# v1.net
KiCad netlist of a schematic drawn in EAGLE
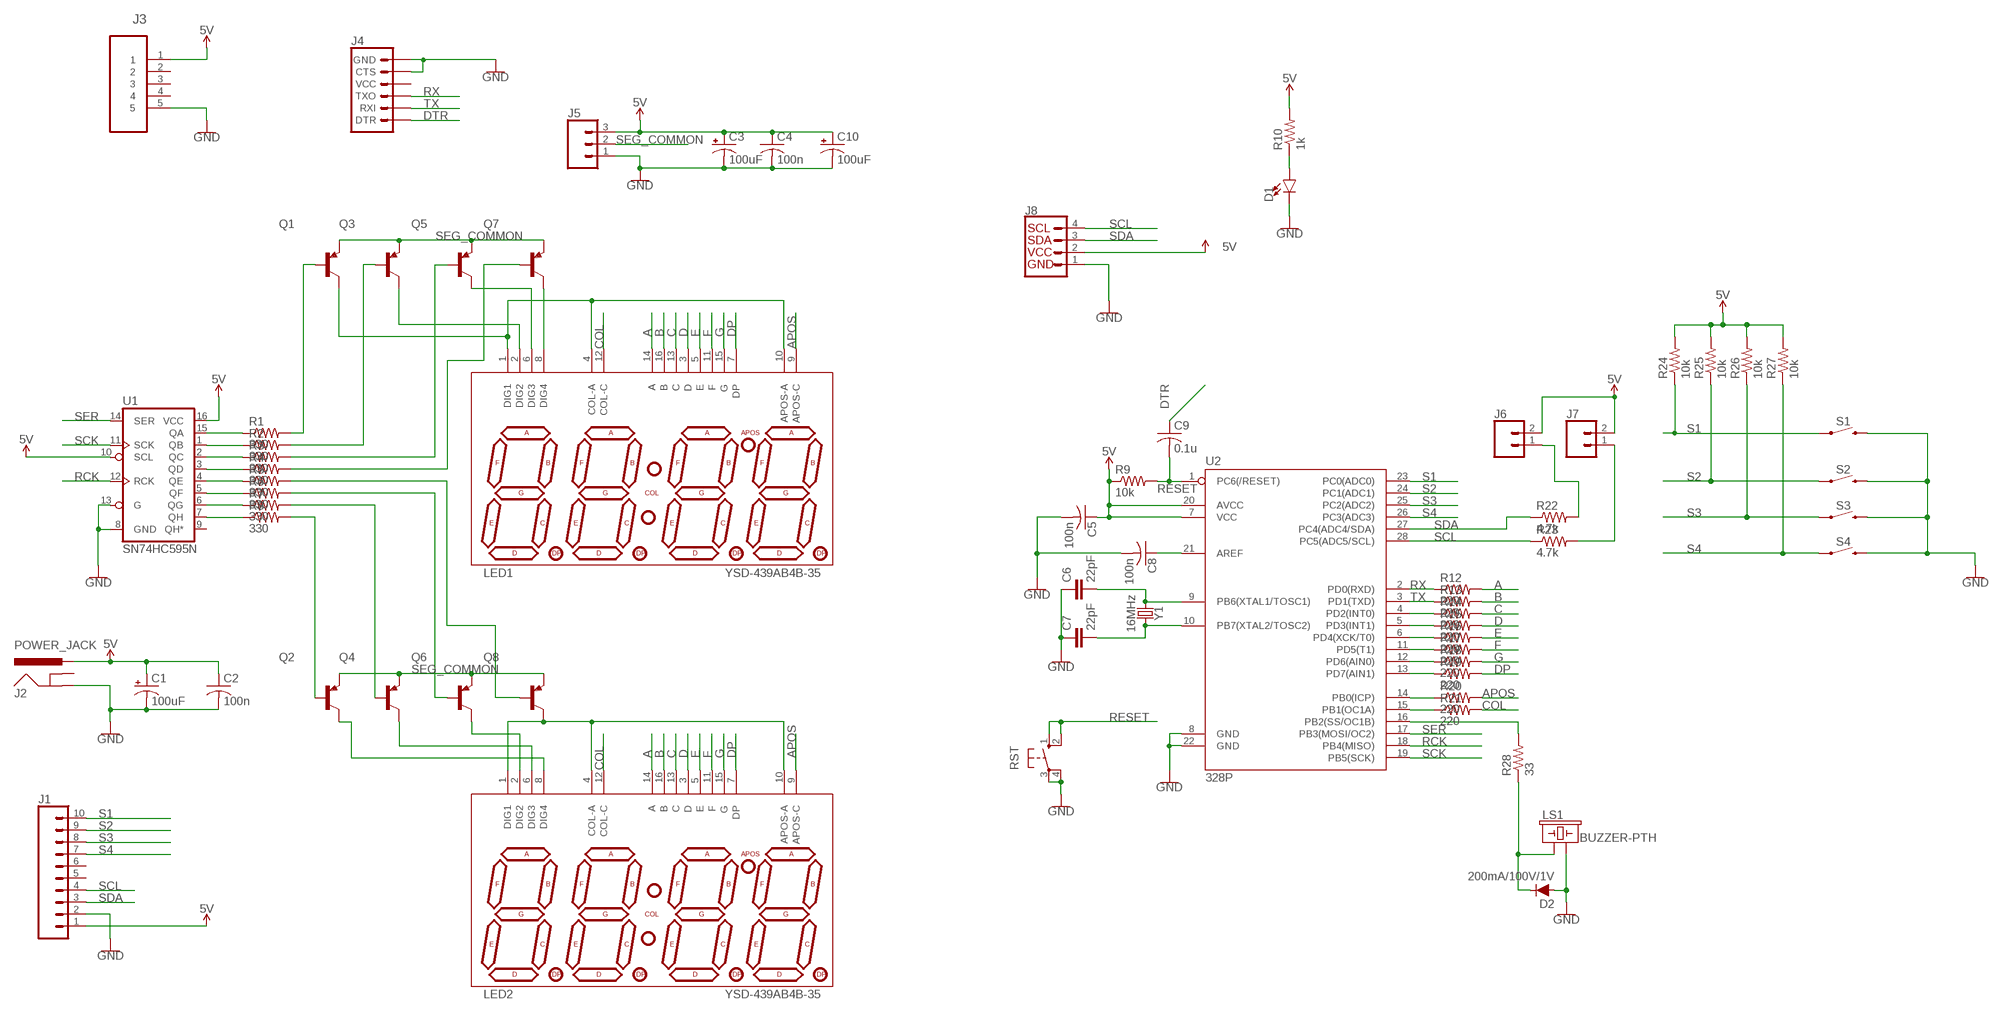
[diagram p0: schematic, sheet 1]

(export (version "E")
  (design (tool "Eeschema 10.0.6"))
  (components
    (comp (ref "C1")
      (value "100uF")
      (footprint "eagle-import:CPOL-RADIAL-2.5MM-6.5MM")
      (libsource (lib "eagle-import") (part "100UF-POLAR-RADIAL-2.5MM-25V-20%"))
    )
    (comp (ref "C2")
      (value "100n")
      (footprint "eagle-import:C025-025X050")
      (libsource (lib "eagle-import") (part "C-US025-025X050"))
    )
    (comp (ref "C3")
      (value "100uF")
      (footprint "eagle-import:CPOL-RADIAL-2.5MM-6.5MM")
      (libsource (lib "eagle-import") (part "100UF-POLAR-RADIAL-2.5MM-25V-20%"))
    )
    (comp (ref "C4")
      (value "100n")
      (footprint "eagle-import:C025-025X050")
      (libsource (lib "eagle-import") (part "C-US025-025X050"))
    )
    (comp (ref "C5")
      (value "100n")
      (footprint "eagle-import:C025-025X050")
      (libsource (lib "eagle-import") (part "C-US025-025X050"))
    )
    (comp (ref "C6")
      (value "22pF")
      (footprint "eagle-import:CAP-PTH-2.54")
      (libsource (lib "eagle-import") (part "22PF-PTH-2.54MM-200V-5%"))
    )
    (comp (ref "C7")
      (value "22pF")
      (footprint "eagle-import:CAP-PTH-2.54")
      (libsource (lib "eagle-import") (part "22PF-PTH-2.54MM-200V-5%"))
    )
    (comp (ref "C8")
      (value "100n")
      (footprint "eagle-import:C025-025X050")
      (libsource (lib "eagle-import") (part "C-US025-025X050"))
    )
    (comp (ref "C9")
      (value "0.1u")
      (footprint "eagle-import:C025-025X050")
      (libsource (lib "eagle-import") (part "C-US025-025X050"))
    )
    (comp (ref "C10")
      (value "100uF")
      (footprint "eagle-import:CPOL-RADIAL-2.5MM-6.5MM")
      (libsource (lib "eagle-import") (part "100UF-POLAR-RADIAL-2.5MM-25V-20%"))
    )
    (comp (ref "D1")
      (value "LED3MM")
      (footprint "eagle-import:LED_3MM")
      (libsource (lib "eagle-import") (part "LED3MM"))
    )
    (comp (ref "D2")
      (value "200mA/100V/1V")
      (footprint "eagle-import:DIODE-1N4148")
      (libsource (lib "eagle-import") (part "DIODE-1N4148"))
    )
    (comp (ref "J1")
      (value "CONN_10\"")
      (footprint "eagle-import:1X10")
      (libsource (lib "eagle-import") (part "CONN_10{dblquote}"))
    )
    (comp (ref "J2")
      (value "POWER_JACK")
      (footprint "eagle-import:POWER_JACK_PTH")
      (libsource (lib "eagle-import") (part "POWER_JACK"))
    )
    (comp (ref "J3")
      (value "47346-0001")
      (footprint "eagle-import:MOLEX_47346-0001")
      (libsource (lib "eagle-import") (part "47346-0001"))
    )
    (comp (ref "J4")
      (value "6_PIN_SERIAL_TARGET")
      (footprint "eagle-import:1X06")
      (libsource (lib "eagle-import") (part "6_PIN_SERIAL_TARGET"))
    )
    (comp (ref "J5")
      (value "CONN_03")
      (footprint "eagle-import:1X03")
      (libsource (lib "eagle-import") (part "CONN_03"))
    )
    (comp (ref "J6")
      (value "CONN_02")
      (footprint "eagle-import:1X02")
      (libsource (lib "eagle-import") (part "CONN_02"))
    )
    (comp (ref "J7")
      (value "CONN_02")
      (footprint "eagle-import:1X02")
      (libsource (lib "eagle-import") (part "CONN_02"))
    )
    (comp (ref "J8")
      (value "I2C_STANDARD")
      (footprint "eagle-import:1X04")
      (libsource (lib "eagle-import") (part "I2C_STANDARD"))
    )
    (comp (ref "LED1")
      (value "YSD-439AB4B-35")
      (footprint "eagle-import:7-SEGMENT-4DIGIT-YOUNGSUN")
      (libsource (lib "eagle-import") (part "7-SEGMENT-4DIGIT-10MM-BLUE"))
    )
    (comp (ref "LED2")
      (value "YSD-439AB4B-35")
      (footprint "eagle-import:7-SEGMENT-4DIGIT-YOUNGSUN")
      (libsource (lib "eagle-import") (part "7-SEGMENT-4DIGIT-10MM-BLUE"))
    )
    (comp (ref "LS1")
      (value "BUZZER-PTH")
      (footprint "eagle-import:BUZZER-12MM")
      (libsource (lib "eagle-import") (part "BUZZER-PTH"))
    )
    (comp (ref "Q1")
      (value "2N3906")
      (footprint "eagle-import:TO92")
      (libsource (lib "eagle-import") (part "2N3906"))
    )
    (comp (ref "Q2")
      (value "2N3906")
      (footprint "eagle-import:TO92")
      (libsource (lib "eagle-import") (part "2N3906"))
    )
    (comp (ref "Q3")
      (value "2N3906")
      (footprint "eagle-import:TO92")
      (libsource (lib "eagle-import") (part "2N3906"))
    )
    (comp (ref "Q4")
      (value "2N3906")
      (footprint "eagle-import:TO92")
      (libsource (lib "eagle-import") (part "2N3906"))
    )
    (comp (ref "Q5")
      (value "2N3906")
      (footprint "eagle-import:TO92")
      (libsource (lib "eagle-import") (part "2N3906"))
    )
    (comp (ref "Q6")
      (value "2N3906")
      (footprint "eagle-import:TO92")
      (libsource (lib "eagle-import") (part "2N3906"))
    )
    (comp (ref "Q7")
      (value "2N3906")
      (footprint "eagle-import:TO92")
      (libsource (lib "eagle-import") (part "2N3906"))
    )
    (comp (ref "Q8")
      (value "2N3906")
      (footprint "eagle-import:TO92")
      (libsource (lib "eagle-import") (part "2N3906"))
    )
    (comp (ref "R1")
      (value "330")
      (footprint "eagle-import:0204_5")
      (libsource (lib "eagle-import") (part "R-US_0204/5"))
    )
    (comp (ref "R2")
      (value "330")
      (footprint "eagle-import:0204_5")
      (libsource (lib "eagle-import") (part "R-US_0204/5"))
    )
    (comp (ref "R3")
      (value "330")
      (footprint "eagle-import:0204_5")
      (libsource (lib "eagle-import") (part "R-US_0204/5"))
    )
    (comp (ref "R4")
      (value "330")
      (footprint "eagle-import:0204_5")
      (libsource (lib "eagle-import") (part "R-US_0204/5"))
    )
    (comp (ref "R5")
      (value "330")
      (footprint "eagle-import:0204_5")
      (libsource (lib "eagle-import") (part "R-US_0204/5"))
    )
    (comp (ref "R6")
      (value "330")
      (footprint "eagle-import:0204_5")
      (libsource (lib "eagle-import") (part "R-US_0204/5"))
    )
    (comp (ref "R7")
      (value "330")
      (footprint "eagle-import:0204_5")
      (libsource (lib "eagle-import") (part "R-US_0204/5"))
    )
    (comp (ref "R8")
      (value "330")
      (footprint "eagle-import:0204_5")
      (libsource (lib "eagle-import") (part "R-US_0204/5"))
    )
    (comp (ref "R9")
      (value "10k")
      (footprint "eagle-import:0204_5")
      (libsource (lib "eagle-import") (part "R-US_0204/5"))
    )
    (comp (ref "R10")
      (value "1k")
      (footprint "eagle-import:0204_5")
      (libsource (lib "eagle-import") (part "R-US_0204/5"))
    )
    (comp (ref "R12")
      (value "220")
      (footprint "eagle-import:0204_5")
      (libsource (lib "eagle-import") (part "R-US_0204/5"))
    )
    (comp (ref "R13")
      (value "220")
      (footprint "eagle-import:0204_5")
      (libsource (lib "eagle-import") (part "R-US_0204/5"))
    )
    (comp (ref "R14")
      (value "220")
      (footprint "eagle-import:0204_5")
      (libsource (lib "eagle-import") (part "R-US_0204/5"))
    )
    (comp (ref "R15")
      (value "220")
      (footprint "eagle-import:0204_5")
      (libsource (lib "eagle-import") (part "R-US_0204/5"))
    )
    (comp (ref "R16")
      (value "220")
      (footprint "eagle-import:0204_5")
      (libsource (lib "eagle-import") (part "R-US_0204/5"))
    )
    (comp (ref "R17")
      (value "220")
      (footprint "eagle-import:0204_5")
      (libsource (lib "eagle-import") (part "R-US_0204/5"))
    )
    (comp (ref "R18")
      (value "220")
      (footprint "eagle-import:0204_5")
      (libsource (lib "eagle-import") (part "R-US_0204/5"))
    )
    (comp (ref "R19")
      (value "220")
      (footprint "eagle-import:0204_5")
      (libsource (lib "eagle-import") (part "R-US_0204/5"))
    )
    (comp (ref "R20")
      (value "220")
      (footprint "eagle-import:0204_5")
      (libsource (lib "eagle-import") (part "R-US_0204/5"))
    )
    (comp (ref "R21")
      (value "220")
      (footprint "eagle-import:0204_5")
      (libsource (lib "eagle-import") (part "R-US_0204/5"))
    )
    (comp (ref "R22")
      (value "4.7k")
      (footprint "eagle-import:0204_5")
      (libsource (lib "eagle-import") (part "R-US_0204/5"))
    )
    (comp (ref "R23")
      (value "4.7k")
      (footprint "eagle-import:0204_5")
      (libsource (lib "eagle-import") (part "R-US_0204/5"))
    )
    (comp (ref "R24")
      (value "10k")
      (footprint "eagle-import:0204_5")
      (libsource (lib "eagle-import") (part "R-US_0204/5"))
    )
    (comp (ref "R25")
      (value "10k")
      (footprint "eagle-import:0204_5")
      (libsource (lib "eagle-import") (part "R-US_0204/5"))
    )
    (comp (ref "R26")
      (value "10k")
      (footprint "eagle-import:0204_5")
      (libsource (lib "eagle-import") (part "R-US_0204/5"))
    )
    (comp (ref "R27")
      (value "10k")
      (footprint "eagle-import:0204_5")
      (libsource (lib "eagle-import") (part "R-US_0204/5"))
    )
    (comp (ref "R28")
      (value "33")
      (footprint "eagle-import:0204_5")
      (libsource (lib "eagle-import") (part "R-US_0204/5"))
    )
    (comp (ref "RST")
      (value "10-XX")
      (footprint "eagle-import:B3F-10XX")
      (fields (field (name "MPN") "B3F-1000"))
      (libsource (lib "eagle-import") (part "10-XX"))
    )
    (comp (ref "S1")
      (value "MOMENTARY-SWITCH-SPST-PTH-6.0MM")
      (footprint "eagle-import:TACTILE_SWITCH_PTH_6.0MM")
      (libsource (lib "eagle-import") (part "MOMENTARY-SWITCH-SPST-PTH-6.0MM"))
    )
    (comp (ref "S2")
      (value "MOMENTARY-SWITCH-SPST-PTH-6.0MM")
      (footprint "eagle-import:TACTILE_SWITCH_PTH_6.0MM")
      (libsource (lib "eagle-import") (part "MOMENTARY-SWITCH-SPST-PTH-6.0MM"))
    )
    (comp (ref "S3")
      (value "MOMENTARY-SWITCH-SPST-PTH-6.0MM")
      (footprint "eagle-import:TACTILE_SWITCH_PTH_6.0MM")
      (libsource (lib "eagle-import") (part "MOMENTARY-SWITCH-SPST-PTH-6.0MM"))
    )
    (comp (ref "S4")
      (value "MOMENTARY-SWITCH-SPST-PTH-6.0MM")
      (footprint "eagle-import:TACTILE_SWITCH_PTH_6.0MM")
      (libsource (lib "eagle-import") (part "MOMENTARY-SWITCH-SPST-PTH-6.0MM"))
    )
    (comp (ref "U1")
      (value "SN74HC595N")
      (footprint "eagle-import:DIP16")
      (libsource (lib "eagle-import") (part "74595NHC"))
    )
    (comp (ref "U2")
      (value "328P")
      (footprint "eagle-import:DIP28")
      (libsource (lib "eagle-import") (part "ATMEGA328P_PDIP"))
    )
    (comp (ref "Y1")
      (value "16MHz")
      (footprint "eagle-import:HC49US")
      (libsource (lib "eagle-import") (part "CRYSTAL-16MHZPTH-HC49US"))
    )
  )
  (nets
    (net (code "1") (name "/A") (class "Default")
      (node (ref "LED1") (pin "14") (pinfunction "A_14") (pintype "bidirectional"))
      (node (ref "LED2") (pin "14") (pinfunction "A_14") (pintype "bidirectional"))
      (node (ref "R12") (pin "2") (pinfunction "2_2") (pintype "passive"))
    )
    (net (code "2") (name "/APOS") (class "Default")
      (node (ref "LED1") (pin "9") (pinfunction "APOS-C_9") (pintype "bidirectional"))
      (node (ref "LED2") (pin "9") (pinfunction "APOS-C_9") (pintype "bidirectional"))
      (node (ref "R20") (pin "2") (pinfunction "2_2") (pintype "passive"))
    )
    (net (code "3") (name "/B") (class "Default")
      (node (ref "LED1") (pin "16") (pinfunction "B_16") (pintype "bidirectional"))
      (node (ref "LED2") (pin "16") (pinfunction "B_16") (pintype "bidirectional"))
      (node (ref "R13") (pin "2") (pinfunction "2_2") (pintype "passive"))
    )
    (net (code "4") (name "/C") (class "Default")
      (node (ref "LED1") (pin "13") (pinfunction "C_13") (pintype "bidirectional"))
      (node (ref "LED2") (pin "13") (pinfunction "C_13") (pintype "bidirectional"))
      (node (ref "R14") (pin "2") (pinfunction "2_2") (pintype "passive"))
    )
    (net (code "5") (name "/COL") (class "Default")
      (node (ref "LED1") (pin "12") (pinfunction "COL-C_12") (pintype "bidirectional"))
      (node (ref "LED2") (pin "12") (pinfunction "COL-C_12") (pintype "bidirectional"))
      (node (ref "R21") (pin "2") (pinfunction "2_2") (pintype "passive"))
    )
    (net (code "6") (name "/D") (class "Default")
      (node (ref "LED1") (pin "3") (pinfunction "D_3") (pintype "bidirectional"))
      (node (ref "LED2") (pin "3") (pinfunction "D_3") (pintype "bidirectional"))
      (node (ref "R15") (pin "2") (pinfunction "2_2") (pintype "passive"))
    )
    (net (code "7") (name "/DP") (class "Default")
      (node (ref "LED1") (pin "7") (pinfunction "DP_7") (pintype "bidirectional"))
      (node (ref "LED2") (pin "7") (pinfunction "DP_7") (pintype "bidirectional"))
      (node (ref "R19") (pin "2") (pinfunction "2_2") (pintype "passive"))
    )
    (net (code "8") (name "/DTR") (class "Default")
      (node (ref "C9") (pin "1") (pinfunction "1_1") (pintype "passive"))
      (node (ref "J4") (pin "1") (pinfunction "DTR_1") (pintype "passive"))
    )
    (net (code "9") (name "/E") (class "Default")
      (node (ref "LED1") (pin "5") (pinfunction "E_5") (pintype "bidirectional"))
      (node (ref "LED2") (pin "5") (pinfunction "E_5") (pintype "bidirectional"))
      (node (ref "R16") (pin "2") (pinfunction "2_2") (pintype "passive"))
    )
    (net (code "10") (name "/F") (class "Default")
      (node (ref "LED1") (pin "11") (pinfunction "F_11") (pintype "bidirectional"))
      (node (ref "LED2") (pin "11") (pinfunction "F_11") (pintype "bidirectional"))
      (node (ref "R17") (pin "2") (pinfunction "2_2") (pintype "passive"))
    )
    (net (code "11") (name "/G") (class "Default")
      (node (ref "LED1") (pin "15") (pinfunction "G_15") (pintype "bidirectional"))
      (node (ref "LED2") (pin "15") (pinfunction "G_15") (pintype "bidirectional"))
      (node (ref "R18") (pin "2") (pinfunction "2_2") (pintype "passive"))
    )
    (net (code "12") (name "/RCK") (class "Default")
      (node (ref "U1") (pin "12") (pinfunction "RCK_12") (pintype "input"))
      (node (ref "U2") (pin "18") (pinfunction "PB4(MISO)_18") (pintype "bidirectional"))
    )
    (net (code "13") (name "/RESET") (class "Default")
      (node (ref "C9") (pin "2") (pinfunction "2_2") (pintype "passive"))
      (node (ref "R9") (pin "2") (pinfunction "2_2") (pintype "passive"))
      (node (ref "RST") (pin "1") (pinfunction "S_1") (pintype "passive"))
      (node (ref "RST") (pin "2") (pinfunction "S1_2") (pintype "passive"))
      (node (ref "U2") (pin "1") (pinfunction "PC6(/RESET)_1") (pintype "bidirectional"))
    )
    (net (code "14") (name "/RX") (class "Default")
      (node (ref "J4") (pin "3") (pinfunction "TXO_3") (pintype "passive"))
      (node (ref "R12") (pin "1") (pinfunction "1_1") (pintype "passive"))
      (node (ref "U2") (pin "2") (pinfunction "PD0(RXD)_2") (pintype "bidirectional"))
    )
    (net (code "15") (name "/S1") (class "Default")
      (node (ref "J1") (pin "10") (pinfunction "10_10") (pintype "passive"))
      (node (ref "R24") (pin "1") (pinfunction "1_1") (pintype "passive"))
      (node (ref "S1") (pin "1") (pinfunction "1_1") (pintype "passive"))
      (node (ref "U2") (pin "23") (pinfunction "PC0(ADC0)_23") (pintype "bidirectional"))
    )
    (net (code "16") (name "/S2") (class "Default")
      (node (ref "J1") (pin "9") (pinfunction "9_9") (pintype "passive"))
      (node (ref "R25") (pin "1") (pinfunction "1_1") (pintype "passive"))
      (node (ref "S2") (pin "1") (pinfunction "1_1") (pintype "passive"))
      (node (ref "U2") (pin "24") (pinfunction "PC1(ADC1)_24") (pintype "bidirectional"))
    )
    (net (code "17") (name "/S3") (class "Default")
      (node (ref "J1") (pin "8") (pinfunction "8_8") (pintype "passive"))
      (node (ref "R26") (pin "1") (pinfunction "1_1") (pintype "passive"))
      (node (ref "S3") (pin "1") (pinfunction "1_1") (pintype "passive"))
      (node (ref "U2") (pin "25") (pinfunction "PC2(ADC2)_25") (pintype "bidirectional"))
    )
    (net (code "18") (name "/S4") (class "Default")
      (node (ref "J1") (pin "7") (pinfunction "7_7") (pintype "passive"))
      (node (ref "R27") (pin "1") (pinfunction "1_1") (pintype "passive"))
      (node (ref "S4") (pin "1") (pinfunction "1_1") (pintype "passive"))
      (node (ref "U2") (pin "26") (pinfunction "PC3(ADC3)_26") (pintype "bidirectional"))
    )
    (net (code "19") (name "/SCK") (class "Default")
      (node (ref "U1") (pin "11") (pinfunction "SCK_11") (pintype "input"))
      (node (ref "U2") (pin "19") (pinfunction "PB5(SCK)_19") (pintype "bidirectional"))
    )
    (net (code "20") (name "/SCL") (class "Default")
      (node (ref "J1") (pin "4") (pinfunction "4_4") (pintype "passive"))
      (node (ref "J8") (pin "4") (pinfunction "4_4") (pintype "passive"))
      (node (ref "R23") (pin "1") (pinfunction "1_1") (pintype "passive"))
      (node (ref "U2") (pin "28") (pinfunction "PC5(ADC5/SCL)_28") (pintype "bidirectional"))
    )
    (net (code "21") (name "/SDA") (class "Default")
      (node (ref "J1") (pin "3") (pinfunction "3_3") (pintype "passive"))
      (node (ref "J8") (pin "3") (pinfunction "3_3") (pintype "passive"))
      (node (ref "R22") (pin "1") (pinfunction "1_1") (pintype "passive"))
      (node (ref "U2") (pin "27") (pinfunction "PC4(ADC4/SDA)_27") (pintype "bidirectional"))
    )
    (net (code "22") (name "/SEG_COMMON") (class "Default")
      (node (ref "J5") (pin "2") (pinfunction "2_2") (pintype "passive"))
      (node (ref "Q1") (pin "3") (pinfunction "E_3") (pintype "passive"))
      (node (ref "Q2") (pin "3") (pinfunction "E_3") (pintype "passive"))
      (node (ref "Q3") (pin "3") (pinfunction "E_3") (pintype "passive"))
      (node (ref "Q4") (pin "3") (pinfunction "E_3") (pintype "passive"))
      (node (ref "Q5") (pin "3") (pinfunction "E_3") (pintype "passive"))
      (node (ref "Q6") (pin "3") (pinfunction "E_3") (pintype "passive"))
      (node (ref "Q7") (pin "3") (pinfunction "E_3") (pintype "passive"))
      (node (ref "Q8") (pin "3") (pinfunction "E_3") (pintype "passive"))
    )
    (net (code "23") (name "/SER") (class "Default")
      (node (ref "U1") (pin "14") (pinfunction "SER_14") (pintype "input"))
      (node (ref "U2") (pin "17") (pinfunction "PB3(MOSI/OC2)_17") (pintype "bidirectional"))
    )
    (net (code "24") (name "/TX") (class "Default")
      (node (ref "J4") (pin "2") (pinfunction "RXI_2") (pintype "passive"))
      (node (ref "R13") (pin "1") (pinfunction "1_1") (pintype "passive"))
      (node (ref "U2") (pin "3") (pinfunction "PD1(TXD)_3") (pintype "bidirectional"))
    )
    (net (code "25") (name "5V") (class "Default")
      (node (ref "C1") (pin "1") (pinfunction "+_1") (pintype "passive"))
      (node (ref "C10") (pin "1") (pinfunction "+_1") (pintype "passive"))
      (node (ref "C2") (pin "1") (pinfunction "1_1") (pintype "passive"))
      (node (ref "C3") (pin "1") (pinfunction "+_1") (pintype "passive"))
      (node (ref "C4") (pin "1") (pinfunction "1_1") (pintype "passive"))
      (node (ref "C5") (pin "1") (pinfunction "1_1") (pintype "passive"))
      (node (ref "J1") (pin "1") (pinfunction "1_1") (pintype "passive"))
      (node (ref "J2") (pin "PWR") (pinfunction "PWR_PWR") (pintype "bidirectional"))
      (node (ref "J3") (pin "1") (pinfunction "1_1") (pintype "input"))
      (node (ref "J5") (pin "3") (pinfunction "3_3") (pintype "passive"))
      (node (ref "J6") (pin "2") (pinfunction "2_2") (pintype "passive"))
      (node (ref "J7") (pin "2") (pinfunction "2_2") (pintype "passive"))
      (node (ref "J8") (pin "2") (pinfunction "2_2") (pintype "power_in"))
      (node (ref "R10") (pin "2") (pinfunction "2_2") (pintype "passive"))
      (node (ref "R24") (pin "2") (pinfunction "2_2") (pintype "passive"))
      (node (ref "R25") (pin "2") (pinfunction "2_2") (pintype "passive"))
      (node (ref "R26") (pin "2") (pinfunction "2_2") (pintype "passive"))
      (node (ref "R27") (pin "2") (pinfunction "2_2") (pintype "passive"))
      (node (ref "R9") (pin "1") (pinfunction "1_1") (pintype "passive"))
      (node (ref "U1") (pin "10") (pinfunction "SCL_10") (pintype "input"))
      (node (ref "U1") (pin "16") (pinfunction "VCC_16") (pintype "power_in"))
      (node (ref "U2") (pin "20") (pinfunction "AVCC_20") (pintype "bidirectional"))
      (node (ref "U2") (pin "7") (pinfunction "VCC_7") (pintype "bidirectional"))
    )
    (net (code "26") (name "GND") (class "Default")
      (node (ref "C1") (pin "2") (pinfunction "-_2") (pintype "passive"))
      (node (ref "C10") (pin "2") (pinfunction "-_2") (pintype "passive"))
      (node (ref "C2") (pin "2") (pinfunction "2_2") (pintype "passive"))
      (node (ref "C3") (pin "2") (pinfunction "-_2") (pintype "passive"))
      (node (ref "C4") (pin "2") (pinfunction "2_2") (pintype "passive"))
      (node (ref "C5") (pin "2") (pinfunction "2_2") (pintype "passive"))
      (node (ref "C6") (pin "1") (pinfunction "1_1") (pintype "passive"))
      (node (ref "C7") (pin "1") (pinfunction "1_1") (pintype "passive"))
      (node (ref "C8") (pin "2") (pinfunction "2_2") (pintype "passive"))
      (node (ref "D1") (pin "K") (pinfunction "C_K") (pintype "passive"))
      (node (ref "D2") (pin "A") (pinfunction "A_A") (pintype "passive"))
      (node (ref "J1") (pin "2") (pinfunction "2_2") (pintype "passive"))
      (node (ref "J2") (pin "GND") (pinfunction "GND_GND") (pintype "bidirectional"))
      (node (ref "J3") (pin "5") (pinfunction "5_5") (pintype "input"))
      (node (ref "J4") (pin "5") (pinfunction "CTS_5") (pintype "passive"))
      (node (ref "J4") (pin "6") (pinfunction "GND_6") (pintype "passive"))
      (node (ref "J5") (pin "1") (pinfunction "1_1") (pintype "passive"))
      (node (ref "J8") (pin "1") (pinfunction "1_1") (pintype "power_in"))
      (node (ref "LS1") (pin "-") (pinfunction "2_-") (pintype "passive"))
      (node (ref "RST") (pin "3") (pinfunction "P_3") (pintype "passive"))
      (node (ref "RST") (pin "4") (pinfunction "P1_4") (pintype "passive"))
      (node (ref "S1") (pin "3") (pinfunction "2_3") (pintype "passive"))
      (node (ref "S2") (pin "3") (pinfunction "2_3") (pintype "passive"))
      (node (ref "S3") (pin "3") (pinfunction "2_3") (pintype "passive"))
      (node (ref "S4") (pin "3") (pinfunction "2_3") (pintype "passive"))
      (node (ref "U1") (pin "13") (pinfunction "G_13") (pintype "input"))
      (node (ref "U1") (pin "8") (pinfunction "GND_8") (pintype "power_in"))
      (node (ref "U2") (pin "22") (pinfunction "GND_22") (pintype "bidirectional"))
      (node (ref "U2") (pin "8") (pinfunction "GND_8") (pintype "bidirectional"))
    )
    (net (code "27") (name "Net-(D1-PadA)") (class "Default")
      (node (ref "D1") (pin "A") (pinfunction "A_A") (pintype "passive"))
      (node (ref "R10") (pin "1") (pinfunction "1_1") (pintype "passive"))
    )
    (net (code "28") (name "Net-(J6-Pad1)") (class "Default")
      (node (ref "J6") (pin "1") (pinfunction "1_1") (pintype "passive"))
      (node (ref "R22") (pin "2") (pinfunction "2_2") (pintype "passive"))
    )
    (net (code "29") (name "Net-(J7-Pad1)") (class "Default")
      (node (ref "J7") (pin "1") (pinfunction "1_1") (pintype "passive"))
      (node (ref "R23") (pin "2") (pinfunction "2_2") (pintype "passive"))
    )
    (net (code "30") (name "Net-(LED1-APOS-A)") (class "Default")
      (node (ref "LED1") (pin "1") (pinfunction "DIG1_1") (pintype "bidirectional"))
      (node (ref "LED1") (pin "10") (pinfunction "APOS-A_10") (pintype "bidirectional"))
      (node (ref "LED1") (pin "4") (pinfunction "COL-A_4") (pintype "bidirectional"))
      (node (ref "Q1") (pin "1") (pinfunction "C_1") (pintype "passive"))
    )
    (net (code "31") (name "Net-(LED1-DIG2)") (class "Default")
      (node (ref "LED1") (pin "2") (pinfunction "DIG2_2") (pintype "bidirectional"))
      (node (ref "Q3") (pin "1") (pinfunction "C_1") (pintype "passive"))
    )
    (net (code "32") (name "Net-(LED1-DIG3)") (class "Default")
      (node (ref "LED1") (pin "6") (pinfunction "DIG3_6") (pintype "bidirectional"))
      (node (ref "Q5") (pin "1") (pinfunction "C_1") (pintype "passive"))
    )
    (net (code "33") (name "Net-(LED1-DIG4)") (class "Default")
      (node (ref "LED1") (pin "8") (pinfunction "DIG4_8") (pintype "bidirectional"))
      (node (ref "Q7") (pin "1") (pinfunction "C_1") (pintype "passive"))
    )
    (net (code "34") (name "Net-(LED2-APOS-A)") (class "Default")
      (node (ref "LED2") (pin "1") (pinfunction "DIG1_1") (pintype "bidirectional"))
      (node (ref "LED2") (pin "10") (pinfunction "APOS-A_10") (pintype "bidirectional"))
      (node (ref "LED2") (pin "4") (pinfunction "COL-A_4") (pintype "bidirectional"))
      (node (ref "Q8") (pin "1") (pinfunction "C_1") (pintype "passive"))
    )
    (net (code "35") (name "Net-(LED2-DIG2)") (class "Default")
      (node (ref "LED2") (pin "2") (pinfunction "DIG2_2") (pintype "bidirectional"))
      (node (ref "Q6") (pin "1") (pinfunction "C_1") (pintype "passive"))
    )
    (net (code "36") (name "Net-(LED2-DIG3)") (class "Default")
      (node (ref "LED2") (pin "6") (pinfunction "DIG3_6") (pintype "bidirectional"))
      (node (ref "Q4") (pin "1") (pinfunction "C_1") (pintype "passive"))
    )
    (net (code "37") (name "Net-(LED2-DIG4)") (class "Default")
      (node (ref "LED2") (pin "8") (pinfunction "DIG4_8") (pintype "bidirectional"))
      (node (ref "Q2") (pin "1") (pinfunction "C_1") (pintype "passive"))
    )
    (net (code "38") (name "Net-(LS1-1)") (class "Default")
      (node (ref "D2") (pin "C") (pinfunction "C_C") (pintype "passive"))
      (node (ref "LS1") (pin "+") (pinfunction "1_+") (pintype "passive"))
      (node (ref "R28") (pin "1") (pinfunction "1_1") (pintype "passive"))
    )
    (net (code "39") (name "Net-(Q1-B)") (class "Default")
      (node (ref "Q1") (pin "2") (pinfunction "B_2") (pintype "passive"))
      (node (ref "R1") (pin "2") (pinfunction "2_2") (pintype "passive"))
    )
    (net (code "40") (name "Net-(Q2-B)") (class "Default")
      (node (ref "Q2") (pin "2") (pinfunction "B_2") (pintype "passive"))
      (node (ref "R8") (pin "2") (pinfunction "2_2") (pintype "passive"))
    )
    (net (code "41") (name "Net-(Q3-B)") (class "Default")
      (node (ref "Q3") (pin "2") (pinfunction "B_2") (pintype "passive"))
      (node (ref "R2") (pin "2") (pinfunction "2_2") (pintype "passive"))
    )
    (net (code "42") (name "Net-(Q4-B)") (class "Default")
      (node (ref "Q4") (pin "2") (pinfunction "B_2") (pintype "passive"))
      (node (ref "R7") (pin "2") (pinfunction "2_2") (pintype "passive"))
    )
    (net (code "43") (name "Net-(Q5-B)") (class "Default")
      (node (ref "Q5") (pin "2") (pinfunction "B_2") (pintype "passive"))
      (node (ref "R3") (pin "2") (pinfunction "2_2") (pintype "passive"))
    )
    (net (code "44") (name "Net-(Q6-B)") (class "Default")
      (node (ref "Q6") (pin "2") (pinfunction "B_2") (pintype "passive"))
      (node (ref "R6") (pin "2") (pinfunction "2_2") (pintype "passive"))
    )
    (net (code "45") (name "Net-(Q7-B)") (class "Default")
      (node (ref "Q7") (pin "2") (pinfunction "B_2") (pintype "passive"))
      (node (ref "R4") (pin "2") (pinfunction "2_2") (pintype "passive"))
    )
    (net (code "46") (name "Net-(Q8-B)") (class "Default")
      (node (ref "Q8") (pin "2") (pinfunction "B_2") (pintype "passive"))
      (node (ref "R5") (pin "2") (pinfunction "2_2") (pintype "passive"))
    )
    (net (code "47") (name "Net-(U1-QA)") (class "Default")
      (node (ref "R1") (pin "1") (pinfunction "1_1") (pintype "passive"))
      (node (ref "U1") (pin "15") (pinfunction "QA_15") (pintype "tri_state"))
    )
    (net (code "48") (name "Net-(U1-QB)") (class "Default")
      (node (ref "R2") (pin "1") (pinfunction "1_1") (pintype "passive"))
      (node (ref "U1") (pin "1") (pinfunction "QB_1") (pintype "tri_state"))
    )
    (net (code "49") (name "Net-(U1-QC)") (class "Default")
      (node (ref "R3") (pin "1") (pinfunction "1_1") (pintype "passive"))
      (node (ref "U1") (pin "2") (pinfunction "QC_2") (pintype "tri_state"))
    )
    (net (code "50") (name "Net-(U1-QD)") (class "Default")
      (node (ref "R4") (pin "1") (pinfunction "1_1") (pintype "passive"))
      (node (ref "U1") (pin "3") (pinfunction "QD_3") (pintype "tri_state"))
    )
    (net (code "51") (name "Net-(U1-QE)") (class "Default")
      (node (ref "R5") (pin "1") (pinfunction "1_1") (pintype "passive"))
      (node (ref "U1") (pin "4") (pinfunction "QE_4") (pintype "tri_state"))
    )
    (net (code "52") (name "Net-(U1-QF)") (class "Default")
      (node (ref "R6") (pin "1") (pinfunction "1_1") (pintype "passive"))
      (node (ref "U1") (pin "5") (pinfunction "QF_5") (pintype "tri_state"))
    )
    (net (code "53") (name "Net-(U1-QG)") (class "Default")
      (node (ref "R7") (pin "1") (pinfunction "1_1") (pintype "passive"))
      (node (ref "U1") (pin "6") (pinfunction "QG_6") (pintype "tri_state"))
    )
    (net (code "54") (name "Net-(U1-QH)") (class "Default")
      (node (ref "R8") (pin "1") (pinfunction "1_1") (pintype "passive"))
      (node (ref "U1") (pin "7") (pinfunction "QH_7") (pintype "tri_state"))
    )
    (net (code "55") (name "Net-(U2-AREF)") (class "Default")
      (node (ref "C8") (pin "1") (pinfunction "1_1") (pintype "passive"))
      (node (ref "U2") (pin "21") (pinfunction "AREF_21") (pintype "bidirectional"))
    )
    (net (code "56") (name "Net-(U2-PB0(ICP))") (class "Default")
      (node (ref "R20") (pin "1") (pinfunction "1_1") (pintype "passive"))
      (node (ref "U2") (pin "14") (pinfunction "PB0(ICP)_14") (pintype "bidirectional"))
    )
    (net (code "57") (name "Net-(U2-PB1(OC1A))") (class "Default")
      (node (ref "R21") (pin "1") (pinfunction "1_1") (pintype "passive"))
      (node (ref "U2") (pin "15") (pinfunction "PB1(OC1A)_15") (pintype "bidirectional"))
    )
    (net (code "58") (name "Net-(U2-PB2(SS{slash}OC1B))") (class "Default")
      (node (ref "R28") (pin "2") (pinfunction "2_2") (pintype "passive"))
      (node (ref "U2") (pin "16") (pinfunction "PB2(SS/OC1B)_16") (pintype "bidirectional"))
    )
    (net (code "59") (name "Net-(U2-PB6(XTAL1{slash}TOSC1))") (class "Default")
      (node (ref "C6") (pin "2") (pinfunction "2_2") (pintype "passive"))
      (node (ref "U2") (pin "9") (pinfunction "PB6(XTAL1/TOSC1)_9") (pintype "bidirectional"))
      (node (ref "Y1") (pin "1") (pinfunction "1_1") (pintype "passive"))
    )
    (net (code "60") (name "Net-(U2-PB7(XTAL2{slash}TOSC2))") (class "Default")
      (node (ref "C7") (pin "2") (pinfunction "2_2") (pintype "passive"))
      (node (ref "U2") (pin "10") (pinfunction "PB7(XTAL2/TOSC2)_10") (pintype "bidirectional"))
      (node (ref "Y1") (pin "2") (pinfunction "2_2") (pintype "passive"))
    )
    (net (code "61") (name "Net-(U2-PD2(INT0))") (class "Default")
      (node (ref "R14") (pin "1") (pinfunction "1_1") (pintype "passive"))
      (node (ref "U2") (pin "4") (pinfunction "PD2(INT0)_4") (pintype "bidirectional"))
    )
    (net (code "62") (name "Net-(U2-PD3(INT1))") (class "Default")
      (node (ref "R15") (pin "1") (pinfunction "1_1") (pintype "passive"))
      (node (ref "U2") (pin "5") (pinfunction "PD3(INT1)_5") (pintype "bidirectional"))
    )
    (net (code "63") (name "Net-(U2-PD4(XCK{slash}T0))") (class "Default")
      (node (ref "R16") (pin "1") (pinfunction "1_1") (pintype "passive"))
      (node (ref "U2") (pin "6") (pinfunction "PD4(XCK/T0)_6") (pintype "bidirectional"))
    )
    (net (code "64") (name "Net-(U2-PD5(T1))") (class "Default")
      (node (ref "R17") (pin "1") (pinfunction "1_1") (pintype "passive"))
      (node (ref "U2") (pin "11") (pinfunction "PD5(T1)_11") (pintype "bidirectional"))
    )
    (net (code "65") (name "Net-(U2-PD6(AIN0))") (class "Default")
      (node (ref "R18") (pin "1") (pinfunction "1_1") (pintype "passive"))
      (node (ref "U2") (pin "12") (pinfunction "PD6(AIN0)_12") (pintype "bidirectional"))
    )
    (net (code "66") (name "Net-(U2-PD7(AIN1))") (class "Default")
      (node (ref "R19") (pin "1") (pinfunction "1_1") (pintype "passive"))
      (node (ref "U2") (pin "13") (pinfunction "PD7(AIN1)_13") (pintype "bidirectional"))
    )
    (net (code "67") (name "unconnected-(J1-Pad5)") (class "Default")
      (node (ref "J1") (pin "5") (pinfunction "5_5") (pintype "passive"))
    )
    (net (code "68") (name "unconnected-(J1-Pad6)") (class "Default")
      (node (ref "J1") (pin "6") (pinfunction "6_6") (pintype "passive"))
    )
    (net (code "69") (name "unconnected-(J2-PadGNDBREAK)") (class "Default")
      (node (ref "J2") (pin "GNDBREAK") (pinfunction "GNDBREAK_GNDBREAK") (pintype "bidirectional"))
    )
    (net (code "70") (name "unconnected-(J3-Pad2)") (class "Default")
      (node (ref "J3") (pin "2") (pinfunction "2_2") (pintype "input"))
    )
    (net (code "71") (name "unconnected-(J3-Pad3)") (class "Default")
      (node (ref "J3") (pin "3") (pinfunction "3_3") (pintype "input"))
    )
    (net (code "72") (name "unconnected-(J3-Pad4)") (class "Default")
      (node (ref "J3") (pin "4") (pinfunction "4_4") (pintype "input"))
    )
    (net (code "73") (name "unconnected-(J4-VCC-Pad4)") (class "Default")
      (node (ref "J4") (pin "4") (pinfunction "VCC_4") (pintype "passive"))
    )
    (net (code "74") (name "unconnected-(U1-QH*-Pad9)") (class "Default")
      (node (ref "U1") (pin "9") (pinfunction "QH*_9") (pintype "tri_state"))
    )
  )
)
